# 15_Raspberry_Pi_Interface.net
KiCad netlist of a schematic drawn in Altium Designer
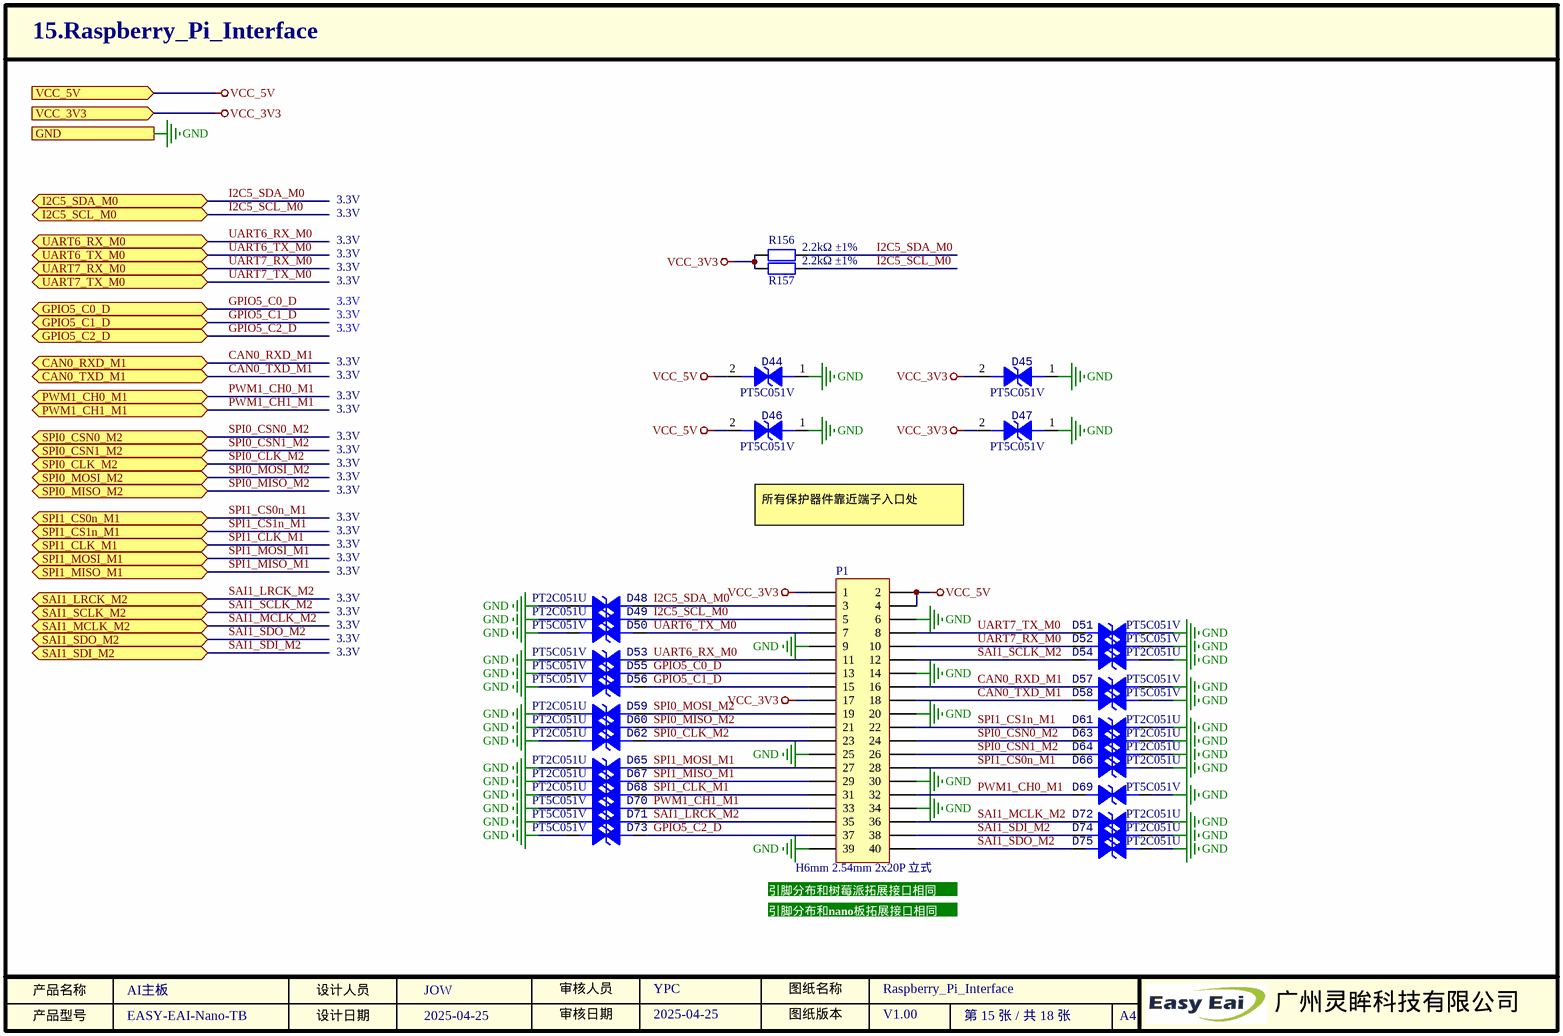
[diagram p0: 15.Raspberry_Pi_Interface.SchDoc]

(export (version "E")
  (design (tool "Eeschema 10.0.6"))
  (components
    (comp (ref "D44")
      (value "PT5C051V")
      (footprint "SOD-523")
      (description "SPZL001155")
      (fields (field (name "型号") "PT5C051V"))
      (libsource (lib "") (part "PT5C051V_1"))
    )
    (comp (ref "D45")
      (value "PT5C051V")
      (footprint "SOD-523")
      (description "SPZL001155")
      (fields (field (name "型号") "PT5C051V"))
      (libsource (lib "") (part "PT5C051V_1"))
    )
    (comp (ref "D46")
      (value "PT5C051V")
      (footprint "SOD-523")
      (description "SPZL001155")
      (fields (field (name "型号") "PT5C051V"))
      (libsource (lib "") (part "PT5C051V_1"))
    )
    (comp (ref "D47")
      (value "PT5C051V")
      (footprint "SOD-523")
      (description "SPZL001155")
      (fields (field (name "型号") "PT5C051V"))
      (libsource (lib "") (part "PT5C051V_1"))
    )
    (comp (ref "D48")
      (value "PT2C051U")
      (footprint "DFN1006")
      (description "SPZL001147")
      (fields (field (name "型号") "PT2C051U"))
      (libsource (lib "ESD_EASY-EAI") (part "PT2C051U"))
    )
    (comp (ref "D49")
      (value "PT2C051U")
      (footprint "DFN1006")
      (description "SPZL001147")
      (fields (field (name "型号") "PT2C051U"))
      (libsource (lib "ESD_EASY-EAI") (part "PT2C051U"))
    )
    (comp (ref "D50")
      (value "PT5C051V")
      (footprint "SOD-523")
      (description "SPZL001155")
      (fields (field (name "型号") "PT5C051V"))
      (libsource (lib "ESD_EASY-EAI") (part "PT5C051V"))
    )
    (comp (ref "D51")
      (value "PT5C051V")
      (footprint "SOD-523")
      (description "SPZL001155")
      (fields (field (name "型号") "PT5C051V"))
      (libsource (lib "ESD_EASY-EAI") (part "PT5C051V"))
    )
    (comp (ref "D52")
      (value "PT5C051V")
      (footprint "SOD-523")
      (description "SPZL001155")
      (fields (field (name "型号") "PT5C051V"))
      (libsource (lib "ESD_EASY-EAI") (part "PT5C051V"))
    )
    (comp (ref "D53")
      (value "PT5C051V")
      (footprint "SOD-523")
      (description "SPZL001155")
      (fields (field (name "型号") "PT5C051V"))
      (libsource (lib "ESD_EASY-EAI") (part "PT5C051V"))
    )
    (comp (ref "D54")
      (value "PT2C051U")
      (footprint "DFN1006")
      (description "SPZL001147")
      (fields (field (name "型号") "PT2C051U"))
      (libsource (lib "ESD_EASY-EAI") (part "PT2C051U"))
    )
    (comp (ref "D55")
      (value "PT5C051V")
      (footprint "SOD-523")
      (description "SPZL001155")
      (fields (field (name "型号") "PT5C051V"))
      (libsource (lib "ESD_EASY-EAI") (part "PT5C051V"))
    )
    (comp (ref "D56")
      (value "PT5C051V")
      (footprint "SOD-523")
      (description "SPZL001155")
      (fields (field (name "型号") "PT5C051V"))
      (libsource (lib "ESD_EASY-EAI") (part "PT5C051V"))
    )
    (comp (ref "D57")
      (value "PT5C051V")
      (footprint "SOD-523")
      (description "SPZL001155")
      (fields (field (name "型号") "PT5C051V"))
      (libsource (lib "ESD_EASY-EAI") (part "PT5C051V"))
    )
    (comp (ref "D58")
      (value "PT5C051V")
      (footprint "SOD-523")
      (description "SPZL001155")
      (fields (field (name "型号") "PT5C051V"))
      (libsource (lib "ESD_EASY-EAI") (part "PT5C051V"))
    )
    (comp (ref "D59")
      (value "PT2C051U")
      (footprint "DFN1006")
      (description "SPZL001147")
      (fields (field (name "型号") "PT2C051U"))
      (libsource (lib "ESD_EASY-EAI") (part "PT2C051U"))
    )
    (comp (ref "D60")
      (value "PT2C051U")
      (footprint "DFN1006")
      (description "SPZL001147")
      (fields (field (name "型号") "PT2C051U"))
      (libsource (lib "ESD_EASY-EAI") (part "PT2C051U"))
    )
    (comp (ref "D61")
      (value "PT2C051U")
      (footprint "DFN1006")
      (description "SPZL001147")
      (fields (field (name "型号") "PT2C051U"))
      (libsource (lib "ESD_EASY-EAI") (part "PT2C051U"))
    )
    (comp (ref "D62")
      (value "PT2C051U")
      (footprint "DFN1006")
      (description "SPZL001147")
      (fields (field (name "型号") "PT2C051U"))
      (libsource (lib "ESD_EASY-EAI") (part "PT2C051U"))
    )
    (comp (ref "D63")
      (value "PT2C051U")
      (footprint "DFN1006")
      (description "SPZL001147")
      (fields (field (name "型号") "PT2C051U"))
      (libsource (lib "ESD_EASY-EAI") (part "PT2C051U"))
    )
    (comp (ref "D64")
      (value "PT2C051U")
      (footprint "DFN1006")
      (description "SPZL001147")
      (fields (field (name "型号") "PT2C051U"))
      (libsource (lib "ESD_EASY-EAI") (part "PT2C051U"))
    )
    (comp (ref "D65")
      (value "PT2C051U")
      (footprint "DFN1006")
      (description "SPZL001147")
      (fields (field (name "型号") "PT2C051U"))
      (libsource (lib "ESD_EASY-EAI") (part "PT2C051U"))
    )
    (comp (ref "D66")
      (value "PT2C051U")
      (footprint "DFN1006")
      (description "SPZL001147")
      (fields (field (name "型号") "PT2C051U"))
      (libsource (lib "ESD_EASY-EAI") (part "PT2C051U"))
    )
    (comp (ref "D67")
      (value "PT2C051U")
      (footprint "DFN1006")
      (description "SPZL001147")
      (fields (field (name "型号") "PT2C051U"))
      (libsource (lib "ESD_EASY-EAI") (part "PT2C051U"))
    )
    (comp (ref "D68")
      (value "PT2C051U")
      (footprint "DFN1006")
      (description "SPZL001147")
      (fields (field (name "型号") "PT2C051U"))
      (libsource (lib "ESD_EASY-EAI") (part "PT2C051U"))
    )
    (comp (ref "D69")
      (value "PT5C051V")
      (footprint "SOD-523")
      (description "SPZL001155")
      (fields (field (name "型号") "PT5C051V"))
      (libsource (lib "ESD_EASY-EAI") (part "PT5C051V"))
    )
    (comp (ref "D70")
      (value "PT5C051V")
      (footprint "SOD-523")
      (description "SPZL001155")
      (fields (field (name "型号") "PT5C051V"))
      (libsource (lib "ESD_EASY-EAI") (part "PT5C051V"))
    )
    (comp (ref "D71")
      (value "PT5C051V")
      (footprint "SOD-523")
      (description "SPZL001155")
      (fields (field (name "型号") "PT5C051V"))
      (libsource (lib "ESD_EASY-EAI") (part "PT5C051V"))
    )
    (comp (ref "D72")
      (value "PT2C051U")
      (footprint "DFN1006")
      (description "SPZL001147")
      (fields (field (name "型号") "PT2C051U"))
      (libsource (lib "ESD_EASY-EAI") (part "PT2C051U"))
    )
    (comp (ref "D73")
      (value "PT5C051V")
      (footprint "SOD-523")
      (description "SPZL001155")
      (fields (field (name "型号") "PT5C051V"))
      (libsource (lib "ESD_EASY-EAI") (part "PT5C051V"))
    )
    (comp (ref "D74")
      (value "PT2C051U")
      (footprint "DFN1006")
      (description "SPZL001147")
      (fields (field (name "型号") "PT2C051U"))
      (libsource (lib "ESD_EASY-EAI") (part "PT2C051U"))
    )
    (comp (ref "D75")
      (value "PT2C051U")
      (footprint "DFN1006")
      (description "SPZL001147")
      (fields (field (name "型号") "PT2C051U"))
      (libsource (lib "ESD_EASY-EAI") (part "PT2C051U"))
    )
    (comp (ref "P1")
      (value "B-2100S40P-B110")
      (footprint "HDR-TH_40P-P2.54-V-M-R2-C20-S2.54")
      (description "SPZL000147")
      (fields (field (name "描述") "H6mm 2.54mm 2x20P 立式"))
      (libsource (lib "Connector_EASY-EAI") (part "排针 H6mm 2.54mm 2x20P 立式"))
    )
    (comp (ref "R156")
      (value "AC0402FR-072K2L")
      (footprint "0402_R")
      (description "SPZL000307")
      (fields (field (name "描述") "2.2kΩ ±1%"))
      (libsource (lib "RES_EASY-EAI") (part "0402 2.2kΩ ±1%"))
    )
    (comp (ref "R157")
      (value "AC0402FR-072K2L")
      (footprint "0402_R")
      (description "SPZL000307")
      (fields (field (name "描述") "2.2kΩ ±1%"))
      (libsource (lib "RES_EASY-EAI") (part "0402 2.2kΩ ±1%"))
    )
  )
  (nets
    (net (code "1") (name "/CAN0_RXD_M1") (class "Default")
      (node (ref "D57") (pin "2") (pinfunction "2_2") (pintype "passive"))
      (node (ref "P1") (pin "16") (pinfunction "16_16") (pintype "passive"))
    )
    (net (code "2") (name "/CAN0_TXD_M1") (class "Default")
      (node (ref "D58") (pin "2") (pinfunction "2_2") (pintype "passive"))
      (node (ref "P1") (pin "18") (pinfunction "18_18") (pintype "passive"))
    )
    (net (code "3") (name "/GPIO5_C0_D") (class "Default")
      (node (ref "D55") (pin "2") (pinfunction "2_2") (pintype "passive"))
      (node (ref "P1") (pin "13") (pinfunction "13_13") (pintype "passive"))
    )
    (net (code "4") (name "/GPIO5_C1_D") (class "Default")
      (node (ref "D56") (pin "2") (pinfunction "2_2") (pintype "passive"))
      (node (ref "P1") (pin "15") (pinfunction "15_15") (pintype "passive"))
    )
    (net (code "5") (name "/GPIO5_C2_D") (class "Default")
      (node (ref "D73") (pin "2") (pinfunction "2_2") (pintype "passive"))
      (node (ref "P1") (pin "37") (pinfunction "37_37") (pintype "passive"))
    )
    (net (code "6") (name "/I2C5_SCL_M0") (class "Default")
      (node (ref "D49") (pin "2") (pinfunction "2_2") (pintype "passive"))
      (node (ref "P1") (pin "5") (pinfunction "5_5") (pintype "passive"))
      (node (ref "R157") (pin "2") (pinfunction "2_2") (pintype "passive"))
    )
    (net (code "7") (name "/I2C5_SDA_M0") (class "Default")
      (node (ref "D48") (pin "2") (pinfunction "2_2") (pintype "passive"))
      (node (ref "P1") (pin "3") (pinfunction "3_3") (pintype "passive"))
      (node (ref "R156") (pin "2") (pinfunction "2_2") (pintype "passive"))
    )
    (net (code "8") (name "/PWM1_CH0_M1") (class "Default")
      (node (ref "D69") (pin "2") (pinfunction "2_2") (pintype "passive"))
      (node (ref "P1") (pin "32") (pinfunction "32_32") (pintype "passive"))
    )
    (net (code "9") (name "/PWM1_CH1_M1") (class "Default")
      (node (ref "D70") (pin "2") (pinfunction "2_2") (pintype "passive"))
      (node (ref "P1") (pin "33") (pinfunction "33_33") (pintype "passive"))
    )
    (net (code "10") (name "/SAI1_LRCK_M2") (class "Default")
      (node (ref "D71") (pin "2") (pinfunction "2_2") (pintype "passive"))
      (node (ref "P1") (pin "35") (pinfunction "35_35") (pintype "passive"))
    )
    (net (code "11") (name "/SAI1_MCLK_M2") (class "Default")
      (node (ref "D72") (pin "1") (pinfunction "1_1") (pintype "passive"))
      (node (ref "P1") (pin "36") (pinfunction "36_36") (pintype "passive"))
    )
    (net (code "12") (name "/SAI1_SCLK_M2") (class "Default")
      (node (ref "D54") (pin "1") (pinfunction "1_1") (pintype "passive"))
      (node (ref "P1") (pin "12") (pinfunction "12_12") (pintype "passive"))
    )
    (net (code "13") (name "/SAI1_SDI_M2") (class "Default")
      (node (ref "D74") (pin "1") (pinfunction "1_1") (pintype "passive"))
      (node (ref "P1") (pin "38") (pinfunction "38_38") (pintype "passive"))
    )
    (net (code "14") (name "/SAI1_SDO_M2") (class "Default")
      (node (ref "D75") (pin "1") (pinfunction "1_1") (pintype "passive"))
      (node (ref "P1") (pin "40") (pinfunction "40_40") (pintype "passive"))
    )
    (net (code "15") (name "/SPI0_CLK_M2") (class "Default")
      (node (ref "D62") (pin "2") (pinfunction "2_2") (pintype "passive"))
      (node (ref "P1") (pin "23") (pinfunction "23_23") (pintype "passive"))
    )
    (net (code "16") (name "/SPI0_CSN0_M2") (class "Default")
      (node (ref "D63") (pin "1") (pinfunction "1_1") (pintype "passive"))
      (node (ref "P1") (pin "24") (pinfunction "24_24") (pintype "passive"))
    )
    (net (code "17") (name "/SPI0_CSN1_M2") (class "Default")
      (node (ref "D64") (pin "1") (pinfunction "1_1") (pintype "passive"))
      (node (ref "P1") (pin "26") (pinfunction "26_26") (pintype "passive"))
    )
    (net (code "18") (name "/SPI0_MISO_M2") (class "Default")
      (node (ref "D60") (pin "2") (pinfunction "2_2") (pintype "passive"))
      (node (ref "P1") (pin "21") (pinfunction "21_21") (pintype "passive"))
    )
    (net (code "19") (name "/SPI0_MOSI_M2") (class "Default")
      (node (ref "D59") (pin "2") (pinfunction "2_2") (pintype "passive"))
      (node (ref "P1") (pin "19") (pinfunction "19_19") (pintype "passive"))
    )
    (net (code "20") (name "/SPI1_CLK_M1") (class "Default")
      (node (ref "D68") (pin "2") (pinfunction "2_2") (pintype "passive"))
      (node (ref "P1") (pin "31") (pinfunction "31_31") (pintype "passive"))
    )
    (net (code "21") (name "/SPI1_CS0n_M1") (class "Default")
      (node (ref "D66") (pin "1") (pinfunction "1_1") (pintype "passive"))
      (node (ref "P1") (pin "28") (pinfunction "28_28") (pintype "passive"))
    )
    (net (code "22") (name "/SPI1_CS1n_M1") (class "Default")
      (node (ref "D61") (pin "1") (pinfunction "1_1") (pintype "passive"))
      (node (ref "P1") (pin "22") (pinfunction "22_22") (pintype "passive"))
    )
    (net (code "23") (name "/SPI1_MISO_M1") (class "Default")
      (node (ref "D67") (pin "2") (pinfunction "2_2") (pintype "passive"))
      (node (ref "P1") (pin "29") (pinfunction "29_29") (pintype "passive"))
    )
    (net (code "24") (name "/SPI1_MOSI_M1") (class "Default")
      (node (ref "D65") (pin "2") (pinfunction "2_2") (pintype "passive"))
      (node (ref "P1") (pin "27") (pinfunction "27_27") (pintype "passive"))
    )
    (net (code "25") (name "/UART6_RX_M0") (class "Default")
      (node (ref "D53") (pin "2") (pinfunction "2_2") (pintype "passive"))
      (node (ref "P1") (pin "11") (pinfunction "11_11") (pintype "passive"))
    )
    (net (code "26") (name "/UART6_TX_M0") (class "Default")
      (node (ref "D50") (pin "2") (pinfunction "2_2") (pintype "passive"))
      (node (ref "P1") (pin "7") (pinfunction "7_7") (pintype "passive"))
    )
    (net (code "27") (name "/UART7_RX_M0") (class "Default")
      (node (ref "D52") (pin "2") (pinfunction "2_2") (pintype "passive"))
      (node (ref "P1") (pin "10") (pinfunction "10_10") (pintype "passive"))
    )
    (net (code "28") (name "/UART7_TX_M0") (class "Default")
      (node (ref "D51") (pin "2") (pinfunction "2_2") (pintype "passive"))
      (node (ref "P1") (pin "8") (pinfunction "8_8") (pintype "passive"))
    )
    (net (code "29") (name "GND") (class "Default")
      (node (ref "D44") (pin "1") (pinfunction "1_1") (pintype "passive"))
      (node (ref "D45") (pin "1") (pinfunction "1_1") (pintype "passive"))
      (node (ref "D46") (pin "1") (pinfunction "1_1") (pintype "passive"))
      (node (ref "D47") (pin "1") (pinfunction "1_1") (pintype "passive"))
      (node (ref "D48") (pin "1") (pinfunction "1_1") (pintype "passive"))
      (node (ref "D49") (pin "1") (pinfunction "1_1") (pintype "passive"))
      (node (ref "D50") (pin "1") (pinfunction "1_1") (pintype "passive"))
      (node (ref "D51") (pin "1") (pinfunction "1_1") (pintype "passive"))
      (node (ref "D52") (pin "1") (pinfunction "1_1") (pintype "passive"))
      (node (ref "D53") (pin "1") (pinfunction "1_1") (pintype "passive"))
      (node (ref "D54") (pin "2") (pinfunction "2_2") (pintype "passive"))
      (node (ref "D55") (pin "1") (pinfunction "1_1") (pintype "passive"))
      (node (ref "D56") (pin "1") (pinfunction "1_1") (pintype "passive"))
      (node (ref "D57") (pin "1") (pinfunction "1_1") (pintype "passive"))
      (node (ref "D58") (pin "1") (pinfunction "1_1") (pintype "passive"))
      (node (ref "D59") (pin "1") (pinfunction "1_1") (pintype "passive"))
      (node (ref "D60") (pin "1") (pinfunction "1_1") (pintype "passive"))
      (node (ref "D61") (pin "2") (pinfunction "2_2") (pintype "passive"))
      (node (ref "D62") (pin "1") (pinfunction "1_1") (pintype "passive"))
      (node (ref "D63") (pin "2") (pinfunction "2_2") (pintype "passive"))
      (node (ref "D64") (pin "2") (pinfunction "2_2") (pintype "passive"))
      (node (ref "D65") (pin "1") (pinfunction "1_1") (pintype "passive"))
      (node (ref "D66") (pin "2") (pinfunction "2_2") (pintype "passive"))
      (node (ref "D67") (pin "1") (pinfunction "1_1") (pintype "passive"))
      (node (ref "D68") (pin "1") (pinfunction "1_1") (pintype "passive"))
      (node (ref "D69") (pin "1") (pinfunction "1_1") (pintype "passive"))
      (node (ref "D70") (pin "1") (pinfunction "1_1") (pintype "passive"))
      (node (ref "D71") (pin "1") (pinfunction "1_1") (pintype "passive"))
      (node (ref "D72") (pin "2") (pinfunction "2_2") (pintype "passive"))
      (node (ref "D73") (pin "1") (pinfunction "1_1") (pintype "passive"))
      (node (ref "D74") (pin "2") (pinfunction "2_2") (pintype "passive"))
      (node (ref "D75") (pin "2") (pinfunction "2_2") (pintype "passive"))
      (node (ref "P1") (pin "14") (pinfunction "14_14") (pintype "passive"))
      (node (ref "P1") (pin "20") (pinfunction "20_20") (pintype "passive"))
      (node (ref "P1") (pin "25") (pinfunction "25_25") (pintype "passive"))
      (node (ref "P1") (pin "30") (pinfunction "30_30") (pintype "passive"))
      (node (ref "P1") (pin "34") (pinfunction "34_34") (pintype "passive"))
      (node (ref "P1") (pin "39") (pinfunction "39_39") (pintype "passive"))
      (node (ref "P1") (pin "6") (pinfunction "6_6") (pintype "passive"))
      (node (ref "P1") (pin "9") (pinfunction "9_9") (pintype "passive"))
    )
    (net (code "30") (name "VCC_3V3") (class "Default")
      (node (ref "D45") (pin "2") (pinfunction "2_2") (pintype "passive"))
      (node (ref "D47") (pin "2") (pinfunction "2_2") (pintype "passive"))
      (node (ref "P1") (pin "1") (pinfunction "1_1") (pintype "passive"))
      (node (ref "P1") (pin "17") (pinfunction "17_17") (pintype "passive"))
      (node (ref "R156") (pin "1") (pinfunction "1_1") (pintype "passive"))
      (node (ref "R157") (pin "1") (pinfunction "1_1") (pintype "passive"))
    )
    (net (code "31") (name "VCC_5V") (class "Default")
      (node (ref "D44") (pin "2") (pinfunction "2_2") (pintype "passive"))
      (node (ref "D46") (pin "2") (pinfunction "2_2") (pintype "passive"))
      (node (ref "P1") (pin "2") (pinfunction "2_2") (pintype "passive"))
      (node (ref "P1") (pin "4") (pinfunction "4_4") (pintype "passive"))
    )
  )
)
